# untitled.net
KiCad netlist of a schematic drawn in EAGLE
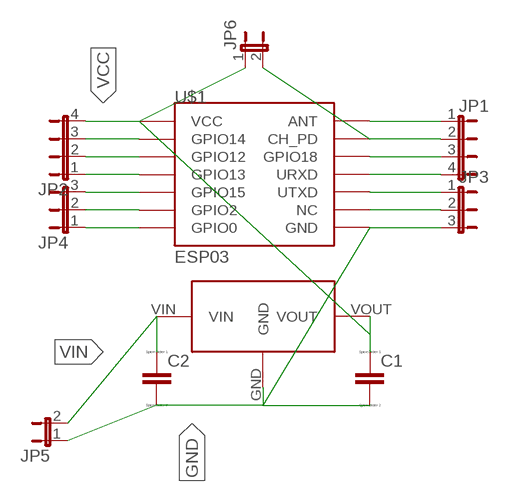
[diagram p0: schematic, sheet 1]

(export (version "E")
  (design (tool "Eeschema 10.0.6"))
  (components
    (comp (ref "C1")
      (value "CC0603")
      (footprint "eagle-import:C0603")
      (libsource (lib "eagle-import") (part "CC0603"))
    )
    (comp (ref "C2")
      (value "CC0603")
      (footprint "eagle-import:C0603")
      (libsource (lib "eagle-import") (part "CC0603"))
    )
    (comp (ref "JP1")
      (value "JP4E")
      (footprint "eagle-import:JP4")
      (libsource (lib "eagle-import") (part "JP4E"))
    )
    (comp (ref "JP2")
      (value "JP4E")
      (footprint "eagle-import:JP4")
      (libsource (lib "eagle-import") (part "JP4E"))
    )
    (comp (ref "JP3")
      (value "JP2E")
      (footprint "eagle-import:JP2")
      (libsource (lib "eagle-import") (part "JP2E"))
    )
    (comp (ref "JP4")
      (value "JP2E")
      (footprint "eagle-import:JP2")
      (libsource (lib "eagle-import") (part "JP2E"))
    )
    (comp (ref "JP5")
      (value "JP1E")
      (footprint "eagle-import:JP1")
      (libsource (lib "eagle-import") (part "JP1E"))
    )
    (comp (ref "JP6")
      (value "JP1E")
      (footprint "eagle-import:JP1")
      (libsource (lib "eagle-import") (part "JP1E"))
    )
    (comp (ref "U$1")
      (value "ESP03")
      (footprint "eagle-import:ESP03")
      (libsource (lib "eagle-import") (part "ESP03"))
    )
    (comp (ref "U$3")
      (value "HT7333")
      (footprint "eagle-import:SOT89")
      (libsource (lib "eagle-import") (part "HT7333"))
    )
  )
  (nets
    (net (code "1") (name "GND") (class "Default")
      (node (ref "C1") (pin "2") (pinfunction "2_2") (pintype "passive"))
      (node (ref "C2") (pin "2") (pinfunction "2_2") (pintype "passive"))
      (node (ref "JP3") (pin "3") (pinfunction "3_3") (pintype "passive"))
      (node (ref "JP5") (pin "1") (pinfunction "1_1") (pintype "passive"))
      (node (ref "U$1") (pin "GND") (pinfunction "GND_GND") (pintype "bidirectional"))
      (node (ref "U$3") (pin "GND") (pinfunction "GND_GND") (pintype "bidirectional"))
    )
    (net (code "2") (name "Net-(JP1-Pad1)") (class "Default")
      (node (ref "JP1") (pin "1") (pinfunction "1_1") (pintype "passive"))
      (node (ref "U$1") (pin "ANT") (pinfunction "ANT_ANT") (pintype "bidirectional"))
    )
    (net (code "3") (name "Net-(JP1-Pad2)") (class "Default")
      (node (ref "JP1") (pin "2") (pinfunction "2_2") (pintype "passive"))
      (node (ref "JP6") (pin "2") (pinfunction "2_2") (pintype "passive"))
      (node (ref "U$1") (pin "CH_PD") (pinfunction "CH_PD_CH_PD") (pintype "bidirectional"))
    )
    (net (code "4") (name "Net-(JP1-Pad3)") (class "Default")
      (node (ref "JP1") (pin "3") (pinfunction "3_3") (pintype "passive"))
      (node (ref "U$1") (pin "GPIO18") (pinfunction "GPIO18_GPIO18") (pintype "bidirectional"))
    )
    (net (code "5") (name "Net-(JP1-Pad4)") (class "Default")
      (node (ref "JP1") (pin "4") (pinfunction "4_4") (pintype "passive"))
      (node (ref "U$1") (pin "URXD") (pinfunction "URXD_URXD") (pintype "bidirectional"))
    )
    (net (code "6") (name "Net-(JP2-Pad1)") (class "Default")
      (node (ref "JP2") (pin "1") (pinfunction "1_1") (pintype "passive"))
      (node (ref "U$1") (pin "GPIO13") (pinfunction "GPIO13_GPIO13") (pintype "bidirectional"))
    )
    (net (code "7") (name "Net-(JP2-Pad2)") (class "Default")
      (node (ref "JP2") (pin "2") (pinfunction "2_2") (pintype "passive"))
      (node (ref "U$1") (pin "GPIO12") (pinfunction "GPIO12_GPIO12") (pintype "bidirectional"))
    )
    (net (code "8") (name "Net-(JP2-Pad3)") (class "Default")
      (node (ref "JP2") (pin "3") (pinfunction "3_3") (pintype "passive"))
      (node (ref "U$1") (pin "GPIO14") (pinfunction "GPIO14_GPIO14") (pintype "bidirectional"))
    )
    (net (code "9") (name "Net-(JP3-Pad1)") (class "Default")
      (node (ref "JP3") (pin "1") (pinfunction "1_1") (pintype "passive"))
      (node (ref "U$1") (pin "UTXD") (pinfunction "UTXD_UTXD") (pintype "bidirectional"))
    )
    (net (code "10") (name "Net-(JP3-Pad2)") (class "Default")
      (node (ref "JP3") (pin "2") (pinfunction "2_2") (pintype "passive"))
      (node (ref "U$1") (pin "NC") (pinfunction "NC_NC") (pintype "bidirectional"))
    )
    (net (code "11") (name "Net-(JP4-Pad1)") (class "Default")
      (node (ref "JP4") (pin "1") (pinfunction "1_1") (pintype "passive"))
      (node (ref "U$1") (pin "GPIO0") (pinfunction "GPIO0_GPIO0") (pintype "bidirectional"))
    )
    (net (code "12") (name "Net-(JP4-Pad2)") (class "Default")
      (node (ref "JP4") (pin "2") (pinfunction "2_2") (pintype "passive"))
      (node (ref "U$1") (pin "GPIO2") (pinfunction "GPIO2_GPIO2") (pintype "bidirectional"))
    )
    (net (code "13") (name "Net-(JP4-Pad3)") (class "Default")
      (node (ref "JP4") (pin "3") (pinfunction "3_3") (pintype "passive"))
      (node (ref "U$1") (pin "GPIO15") (pinfunction "GPIO15_GPIO15") (pintype "bidirectional"))
    )
    (net (code "14") (name "VCC") (class "Default")
      (node (ref "C1") (pin "1") (pinfunction "1_1") (pintype "passive"))
      (node (ref "JP2") (pin "4") (pinfunction "4_4") (pintype "passive"))
      (node (ref "JP6") (pin "1") (pinfunction "1_1") (pintype "passive"))
      (node (ref "U$1") (pin "VCC") (pinfunction "VCC_VCC") (pintype "bidirectional"))
      (node (ref "U$3") (pin "VOUT") (pinfunction "VOUT_VOUT") (pintype "bidirectional"))
    )
    (net (code "15") (name "VIN") (class "Default")
      (node (ref "C2") (pin "1") (pinfunction "1_1") (pintype "passive"))
      (node (ref "JP5") (pin "2") (pinfunction "2_2") (pintype "passive"))
      (node (ref "U$3") (pin "VIN") (pinfunction "VIN_VIN") (pintype "bidirectional"))
    )
  )
)
